# SCH_Type_c_2022-05-16.net
KiCad netlist of a schematic drawn in EasyEDA
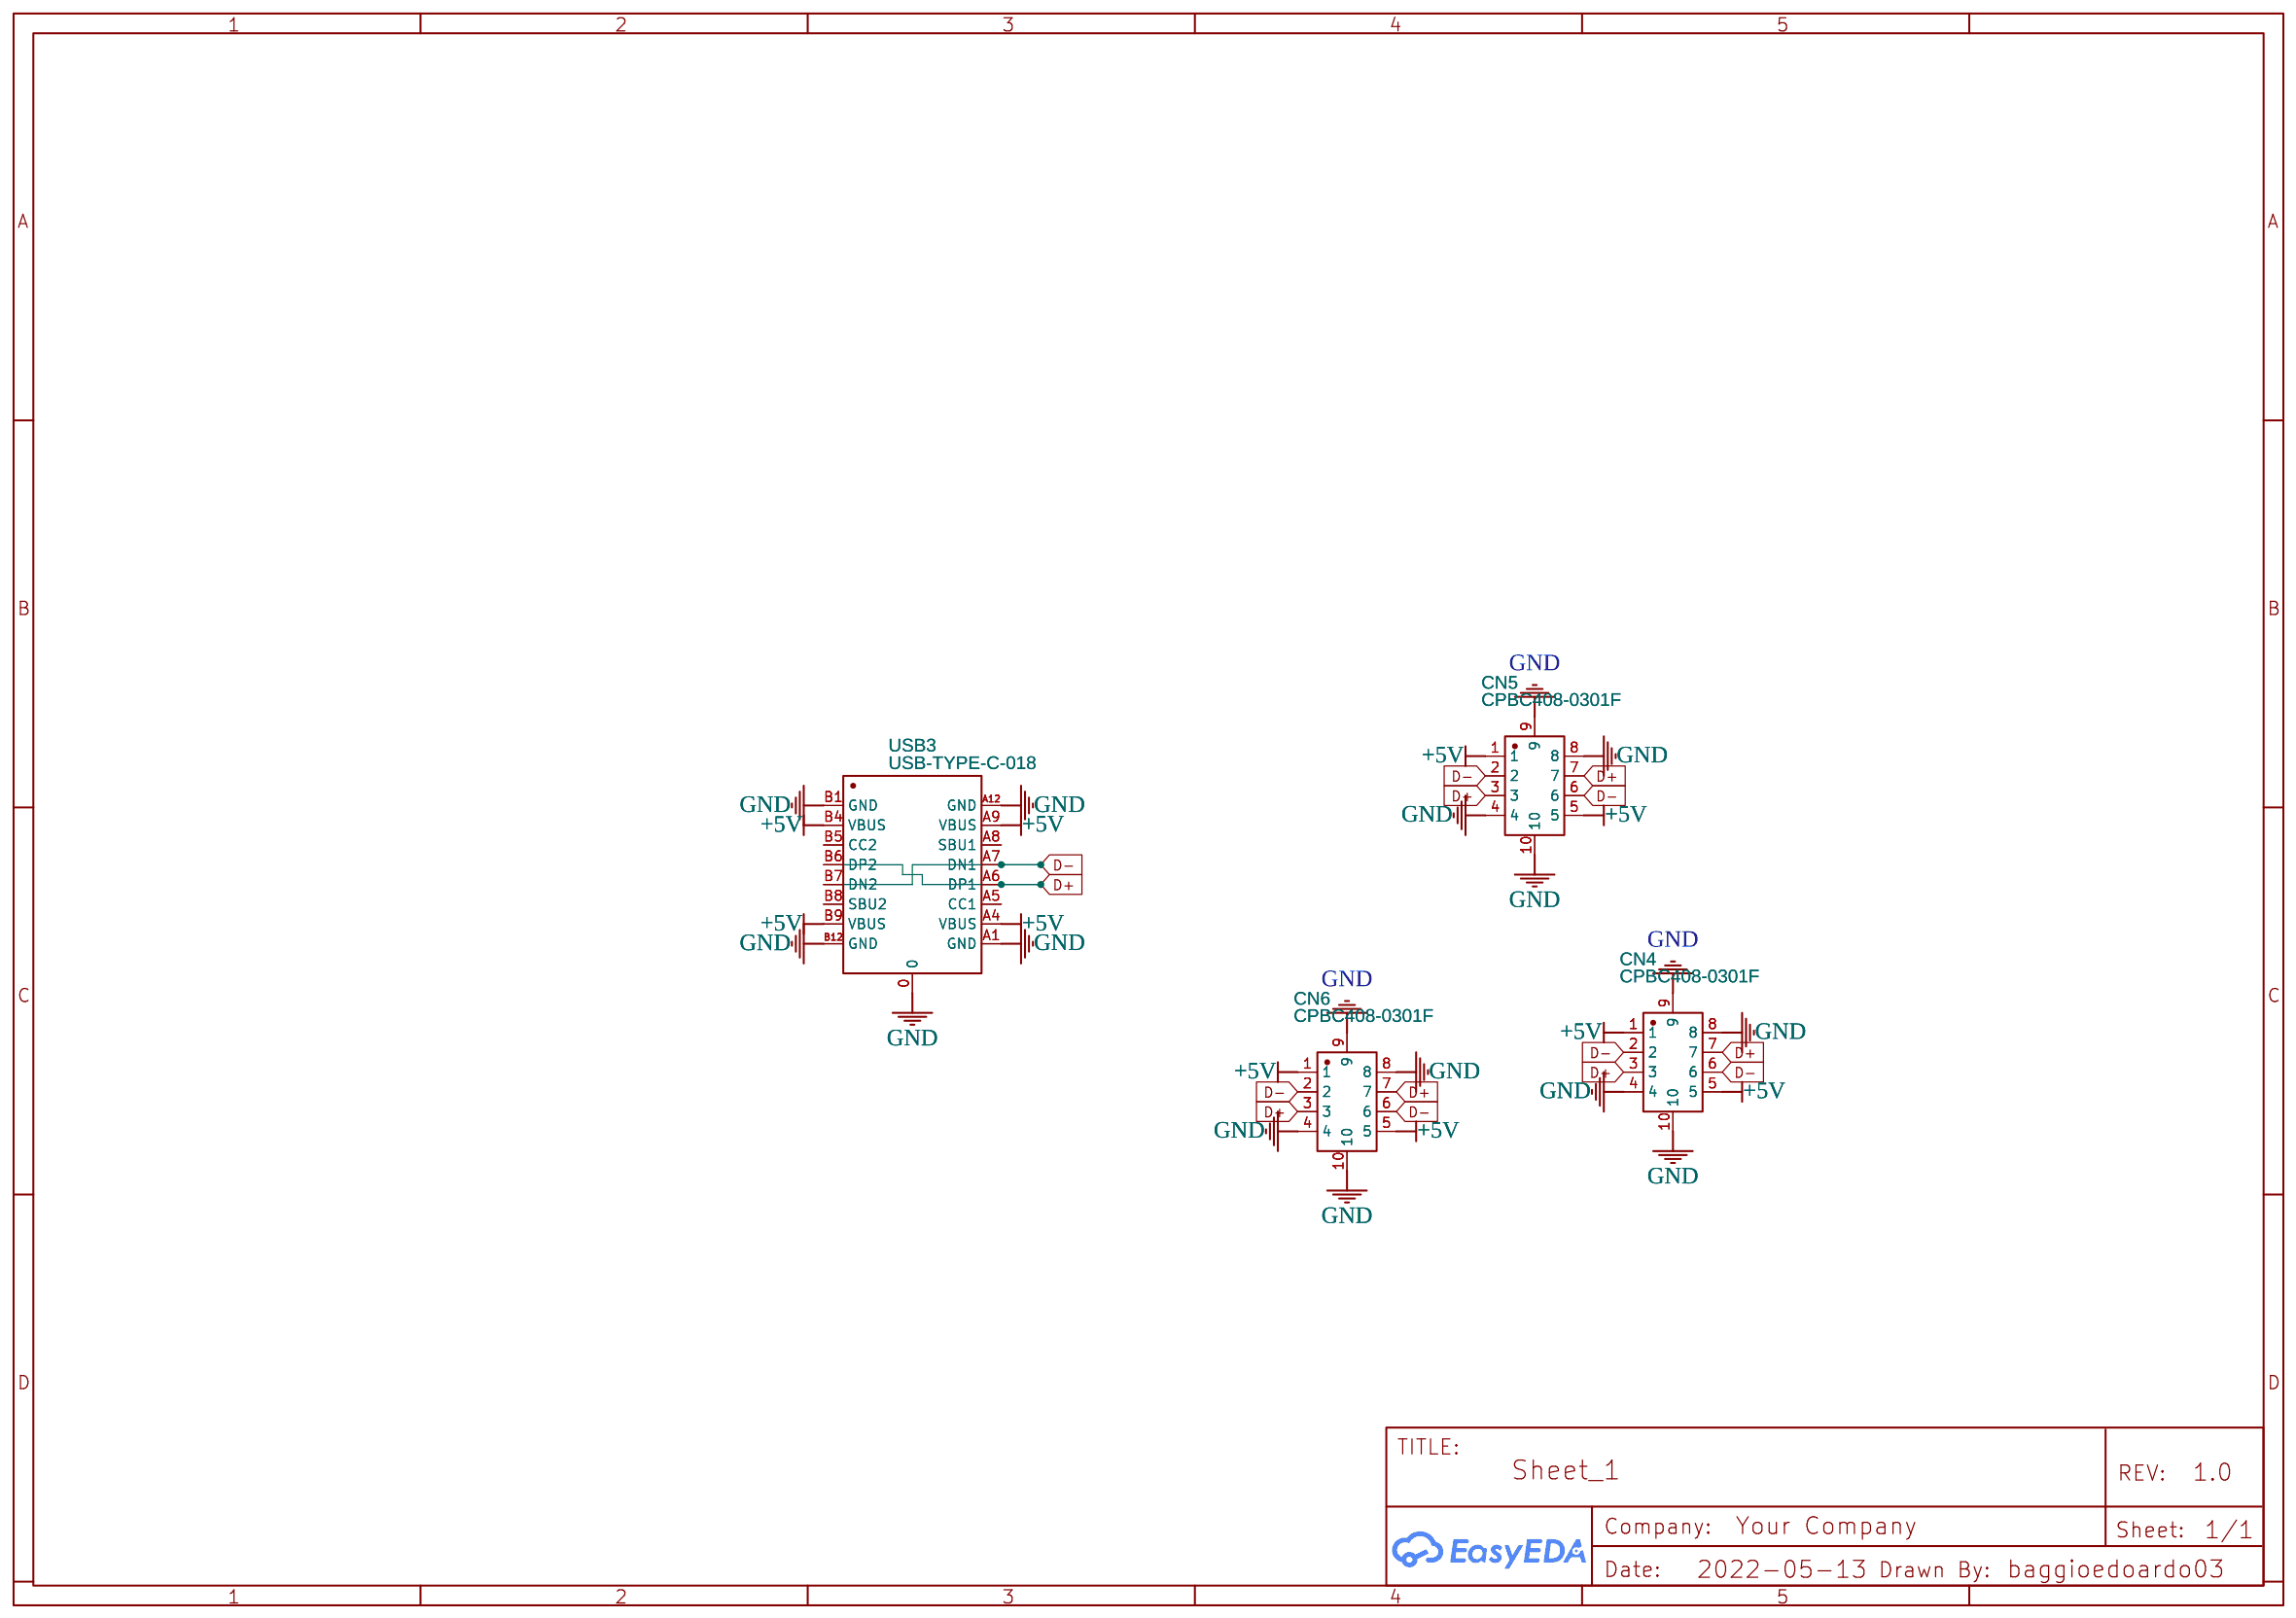
[diagram p0: schematic sheet]

(export (version "E")
  (design (tool "Eeschema 10.0.6"))
  (components
    (comp (ref "CN4")
      (value "CPBC408-0301F")
      (fields (field (name "BOM_Supplier Part") "C841002"))
      (libsource (lib "") (part "CPBC408-0301F"))
    )
    (comp (ref "CN5")
      (value "CPBC408-0301F")
      (fields (field (name "BOM_Supplier Part") "C841002"))
      (libsource (lib "") (part "CPBC408-0301F"))
    )
    (comp (ref "CN6")
      (value "CPBC408-0301F")
      (fields (field (name "BOM_Supplier Part") "C841002"))
      (libsource (lib "") (part "CPBC408-0301F"))
    )
    (comp (ref "USB3")
      (value "USB-TYPE-C-018")
      (fields (field (name "BOM_Supplier Part") "C2927038"))
      (libsource (lib "") (part "USB-TYPE-C-018"))
    )
  )
  (nets
    (net (code "1") (name "+5V") (class "Default")
      (node (ref "CN4") (pin "1") (pinfunction "1_1") (pintype "unspecified"))
      (node (ref "CN4") (pin "5") (pinfunction "5_5") (pintype "unspecified"))
      (node (ref "CN5") (pin "1") (pinfunction "1_1") (pintype "unspecified"))
      (node (ref "CN5") (pin "5") (pinfunction "5_5") (pintype "unspecified"))
      (node (ref "CN6") (pin "1") (pinfunction "1_1") (pintype "unspecified"))
      (node (ref "CN6") (pin "5") (pinfunction "5_5") (pintype "unspecified"))
      (node (ref "USB3") (pin "A4") (pinfunction "VBUS_A4") (pintype "unspecified"))
      (node (ref "USB3") (pin "A9") (pinfunction "VBUS_A9") (pintype "unspecified"))
      (node (ref "USB3") (pin "B4") (pinfunction "VBUS_B4") (pintype "unspecified"))
      (node (ref "USB3") (pin "B9") (pinfunction "VBUS_B9") (pintype "unspecified"))
    )
    (net (code "2") (name "D+") (class "Default")
      (node (ref "CN4") (pin "3") (pinfunction "3_3") (pintype "unspecified"))
      (node (ref "CN4") (pin "7") (pinfunction "7_7") (pintype "unspecified"))
      (node (ref "CN5") (pin "3") (pinfunction "3_3") (pintype "unspecified"))
      (node (ref "CN5") (pin "7") (pinfunction "7_7") (pintype "unspecified"))
      (node (ref "CN6") (pin "3") (pinfunction "3_3") (pintype "unspecified"))
      (node (ref "CN6") (pin "7") (pinfunction "7_7") (pintype "unspecified"))
      (node (ref "USB3") (pin "A6") (pinfunction "DP1_A6") (pintype "unspecified"))
      (node (ref "USB3") (pin "B6") (pinfunction "DP2_B6") (pintype "unspecified"))
    )
    (net (code "3") (name "D-") (class "Default")
      (node (ref "CN4") (pin "2") (pinfunction "2_2") (pintype "unspecified"))
      (node (ref "CN4") (pin "6") (pinfunction "6_6") (pintype "unspecified"))
      (node (ref "CN5") (pin "2") (pinfunction "2_2") (pintype "unspecified"))
      (node (ref "CN5") (pin "6") (pinfunction "6_6") (pintype "unspecified"))
      (node (ref "CN6") (pin "2") (pinfunction "2_2") (pintype "unspecified"))
      (node (ref "CN6") (pin "6") (pinfunction "6_6") (pintype "unspecified"))
      (node (ref "USB3") (pin "A7") (pinfunction "DN1_A7") (pintype "unspecified"))
      (node (ref "USB3") (pin "B7") (pinfunction "DN2_B7") (pintype "unspecified"))
    )
    (net (code "4") (name "GND") (class "Default")
      (node (ref "CN4") (pin "10") (pinfunction "10_10") (pintype "unspecified"))
      (node (ref "CN4") (pin "4") (pinfunction "4_4") (pintype "unspecified"))
      (node (ref "CN4") (pin "8") (pinfunction "8_8") (pintype "unspecified"))
      (node (ref "CN4") (pin "9") (pinfunction "9_9") (pintype "unspecified"))
      (node (ref "CN5") (pin "10") (pinfunction "10_10") (pintype "unspecified"))
      (node (ref "CN5") (pin "4") (pinfunction "4_4") (pintype "unspecified"))
      (node (ref "CN5") (pin "8") (pinfunction "8_8") (pintype "unspecified"))
      (node (ref "CN5") (pin "9") (pinfunction "9_9") (pintype "unspecified"))
      (node (ref "CN6") (pin "10") (pinfunction "10_10") (pintype "unspecified"))
      (node (ref "CN6") (pin "4") (pinfunction "4_4") (pintype "unspecified"))
      (node (ref "CN6") (pin "8") (pinfunction "8_8") (pintype "unspecified"))
      (node (ref "CN6") (pin "9") (pinfunction "9_9") (pintype "unspecified"))
      (node (ref "USB3") (pin "0") (pinfunction "0_0") (pintype "unspecified"))
      (node (ref "USB3") (pin "A1") (pinfunction "GND_A1") (pintype "unspecified"))
      (node (ref "USB3") (pin "A12") (pinfunction "GND_A12") (pintype "unspecified"))
      (node (ref "USB3") (pin "B1") (pinfunction "GND_B1") (pintype "unspecified"))
      (node (ref "USB3") (pin "B12") (pinfunction "GND_B12") (pintype "unspecified"))
    )
    (net (code "5") (name "unconnected-(USB3-CC1-PadA5)") (class "Default")
      (node (ref "USB3") (pin "A5") (pinfunction "CC1_A5") (pintype "unspecified"))
    )
    (net (code "6") (name "unconnected-(USB3-CC2-PadB5)") (class "Default")
      (node (ref "USB3") (pin "B5") (pinfunction "CC2_B5") (pintype "unspecified"))
    )
    (net (code "7") (name "unconnected-(USB3-SBU1-PadA8)") (class "Default")
      (node (ref "USB3") (pin "A8") (pinfunction "SBU1_A8") (pintype "unspecified"))
    )
    (net (code "8") (name "unconnected-(USB3-SBU2-PadB8)") (class "Default")
      (node (ref "USB3") (pin "B8") (pinfunction "SBU2_B8") (pintype "unspecified"))
    )
  )
)
